# endstop-board.net
KiCad netlist of a schematic drawn in EAGLE
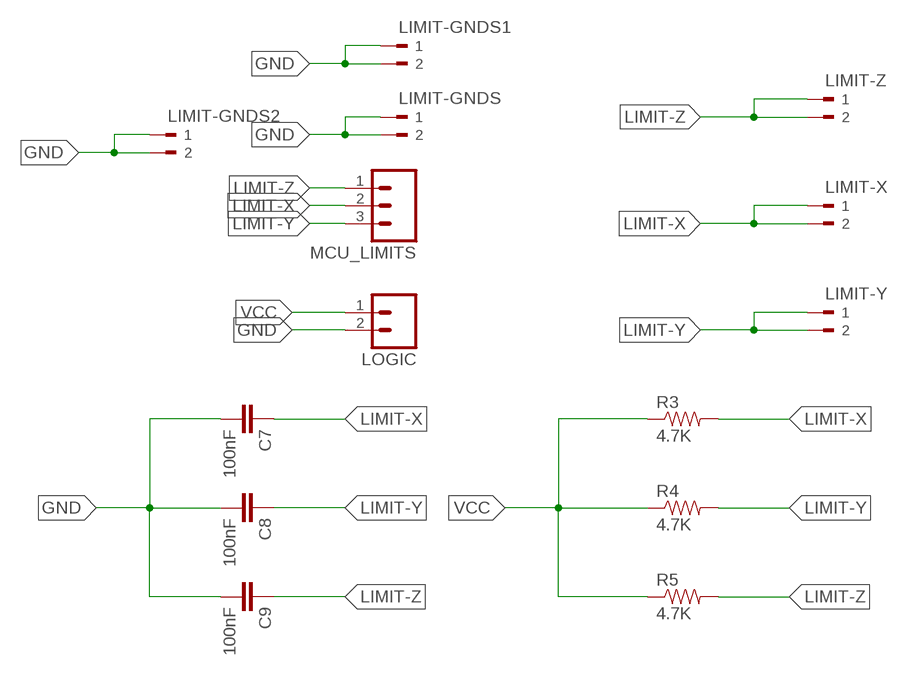
[diagram p0: schematic, sheet 1]

(export (version "E")
  (design (tool "Eeschema 10.0.6"))
  (components
    (comp (ref "C7")
      (value "100nF")
      (footprint "eagle-import:1206")
      (libsource (lib "eagle-import") (part "CAP1206"))
    )
    (comp (ref "C8")
      (value "100nF")
      (footprint "eagle-import:1206")
      (libsource (lib "eagle-import") (part "CAP1206"))
    )
    (comp (ref "C9")
      (value "100nF")
      (footprint "eagle-import:1206")
      (libsource (lib "eagle-import") (part "CAP1206"))
    )
    (comp (ref "LIMIT-GNDS")
      (value "PM5.08/2/90BLK")
      (footprint "eagle-import:WEIDMULLER_PM5.08_2")
      (fields (field (name "MPN") "PM5.08/2/90 BLK"))
      (libsource (lib "eagle-import") (part "PM5.08/2/90BLK"))
    )
    (comp (ref "LIMIT-GNDS1")
      (value "PM5.08/2/90BLK")
      (footprint "eagle-import:WEIDMULLER_PM5.08_2")
      (fields (field (name "MPN") "PM5.08/2/90 BLK"))
      (libsource (lib "eagle-import") (part "PM5.08/2/90BLK"))
    )
    (comp (ref "LIMIT-GNDS2")
      (value "PM5.08/2/90BLK")
      (footprint "eagle-import:WEIDMULLER_PM5.08_2")
      (fields (field (name "MPN") "PM5.08/2/90 BLK"))
      (libsource (lib "eagle-import") (part "PM5.08/2/90BLK"))
    )
    (comp (ref "LIMIT-X")
      (value "PM5.08/2/90BLK")
      (footprint "eagle-import:WEIDMULLER_PM5.08_2")
      (fields (field (name "MPN") "PM5.08/2/90 BLK"))
      (libsource (lib "eagle-import") (part "PM5.08/2/90BLK"))
    )
    (comp (ref "LIMIT-Y")
      (value "PM5.08/2/90BLK")
      (footprint "eagle-import:WEIDMULLER_PM5.08_2")
      (fields (field (name "MPN") "PM5.08/2/90 BLK"))
      (libsource (lib "eagle-import") (part "PM5.08/2/90BLK"))
    )
    (comp (ref "LIMIT-Z")
      (value "PM5.08/2/90BLK")
      (footprint "eagle-import:WEIDMULLER_PM5.08_2")
      (fields (field (name "MPN") "PM5.08/2/90 BLK"))
      (libsource (lib "eagle-import") (part "PM5.08/2/90BLK"))
    )
    (comp (ref "LOGIC")
      (value "M02")
      (footprint "eagle-import:02P")
      (libsource (lib "eagle-import") (part "M02"))
    )
    (comp (ref "MCU_LIMITS")
      (value "M03")
      (footprint "eagle-import:03P")
      (libsource (lib "eagle-import") (part "M03"))
    )
    (comp (ref "R3")
      (value "4.7K")
      (footprint "eagle-import:1206")
      (libsource (lib "eagle-import") (part "RESISTOR1206"))
    )
    (comp (ref "R4")
      (value "4.7K")
      (footprint "eagle-import:1206")
      (libsource (lib "eagle-import") (part "RESISTOR1206"))
    )
    (comp (ref "R5")
      (value "4.7K")
      (footprint "eagle-import:1206")
      (libsource (lib "eagle-import") (part "RESISTOR1206"))
    )
  )
  (nets
    (net (code "1") (name "GND") (class "Default")
      (node (ref "C7") (pin "2") (pinfunction "2_2") (pintype "passive"))
      (node (ref "C8") (pin "2") (pinfunction "2_2") (pintype "passive"))
      (node (ref "C9") (pin "2") (pinfunction "2_2") (pintype "passive"))
      (node (ref "LIMIT-GNDS") (pin "1") (pinfunction "1_1") (pintype "passive"))
      (node (ref "LIMIT-GNDS") (pin "2") (pinfunction "2_2") (pintype "passive"))
      (node (ref "LIMIT-GNDS1") (pin "1") (pinfunction "1_1") (pintype "passive"))
      (node (ref "LIMIT-GNDS1") (pin "2") (pinfunction "2_2") (pintype "passive"))
      (node (ref "LIMIT-GNDS2") (pin "1") (pinfunction "1_1") (pintype "passive"))
      (node (ref "LIMIT-GNDS2") (pin "2") (pinfunction "2_2") (pintype "passive"))
      (node (ref "LOGIC") (pin "2") (pinfunction "2_2") (pintype "passive"))
    )
    (net (code "2") (name "LIMIT-X") (class "Default")
      (node (ref "C7") (pin "1") (pinfunction "1_1") (pintype "passive"))
      (node (ref "LIMIT-X") (pin "1") (pinfunction "1_1") (pintype "passive"))
      (node (ref "LIMIT-X") (pin "2") (pinfunction "2_2") (pintype "passive"))
      (node (ref "MCU_LIMITS") (pin "2") (pinfunction "2_2") (pintype "passive"))
      (node (ref "R3") (pin "2") (pinfunction "2_2") (pintype "passive"))
    )
    (net (code "3") (name "LIMIT-Y") (class "Default")
      (node (ref "C8") (pin "1") (pinfunction "1_1") (pintype "passive"))
      (node (ref "LIMIT-Y") (pin "1") (pinfunction "1_1") (pintype "passive"))
      (node (ref "LIMIT-Y") (pin "2") (pinfunction "2_2") (pintype "passive"))
      (node (ref "MCU_LIMITS") (pin "3") (pinfunction "3_3") (pintype "passive"))
      (node (ref "R4") (pin "2") (pinfunction "2_2") (pintype "passive"))
    )
    (net (code "4") (name "LIMIT-Z") (class "Default")
      (node (ref "C9") (pin "1") (pinfunction "1_1") (pintype "passive"))
      (node (ref "LIMIT-Z") (pin "1") (pinfunction "1_1") (pintype "passive"))
      (node (ref "LIMIT-Z") (pin "2") (pinfunction "2_2") (pintype "passive"))
      (node (ref "MCU_LIMITS") (pin "1") (pinfunction "1_1") (pintype "passive"))
      (node (ref "R5") (pin "2") (pinfunction "2_2") (pintype "passive"))
    )
    (net (code "5") (name "VCC") (class "Default")
      (node (ref "LOGIC") (pin "1") (pinfunction "1_1") (pintype "passive"))
      (node (ref "R3") (pin "1") (pinfunction "1_1") (pintype "passive"))
      (node (ref "R4") (pin "1") (pinfunction "1_1") (pintype "passive"))
      (node (ref "R5") (pin "1") (pinfunction "1_1") (pintype "passive"))
    )
  )
)
